# Untitled.net
KiCad netlist of a schematic drawn in EAGLE
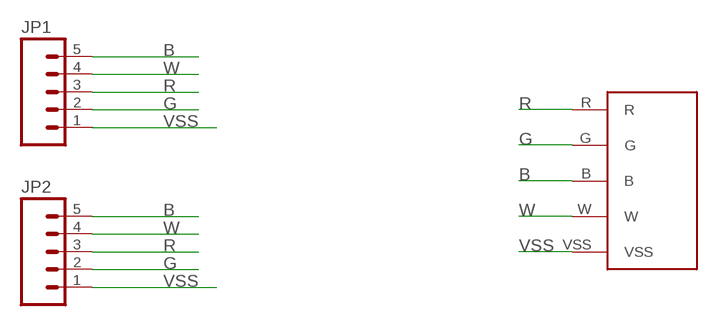
[diagram p0: schematic, sheet 1]

(export (version "E")
  (design (tool "Eeschema 10.0.6"))
  (components
    (comp (ref "JP1")
      (value "M05PTH_LONGPADS")
      (footprint "eagle-import:1X05_LONGPADS")
      (libsource (lib "eagle-import") (part "M05PTH_LONGPADS"))
    )
    (comp (ref "JP2")
      (value "M05PTH_LONGPADS")
      (footprint "eagle-import:1X05_LONGPADS")
      (libsource (lib "eagle-import") (part "M05PTH_LONGPADS"))
    )
    (comp (ref "U$1")
      (value "RGBWSTRIP")
      (footprint "eagle-import:RGBWSTRIP")
      (libsource (lib "eagle-import") (part "RGBWSTRIP"))
    )
  )
  (nets
    (net (code "1") (name "/B") (class "Default")
      (node (ref "JP1") (pin "5") (pinfunction "5_5") (pintype "passive"))
      (node (ref "JP2") (pin "5") (pinfunction "5_5") (pintype "passive"))
      (node (ref "U$1") (pin "B") (pinfunction "B_B") (pintype "bidirectional"))
    )
    (net (code "2") (name "/G") (class "Default")
      (node (ref "JP1") (pin "2") (pinfunction "2_2") (pintype "passive"))
      (node (ref "JP2") (pin "2") (pinfunction "2_2") (pintype "passive"))
      (node (ref "U$1") (pin "G") (pinfunction "G_G") (pintype "bidirectional"))
    )
    (net (code "3") (name "/R") (class "Default")
      (node (ref "JP1") (pin "3") (pinfunction "3_3") (pintype "passive"))
      (node (ref "JP2") (pin "3") (pinfunction "3_3") (pintype "passive"))
      (node (ref "U$1") (pin "R") (pinfunction "R_R") (pintype "bidirectional"))
    )
    (net (code "4") (name "/VSS") (class "Default")
      (node (ref "JP1") (pin "1") (pinfunction "1_1") (pintype "passive"))
      (node (ref "JP2") (pin "1") (pinfunction "1_1") (pintype "passive"))
      (node (ref "U$1") (pin "VSS") (pinfunction "VSS_VSS") (pintype "bidirectional"))
    )
    (net (code "5") (name "/W") (class "Default")
      (node (ref "JP1") (pin "4") (pinfunction "4_4") (pintype "passive"))
      (node (ref "JP2") (pin "4") (pinfunction "4_4") (pintype "passive"))
      (node (ref "U$1") (pin "W") (pinfunction "W_W") (pintype "bidirectional"))
    )
  )
)
